# PhoneRinger_v1-2.net
KiCad netlist of a schematic drawn in EAGLE
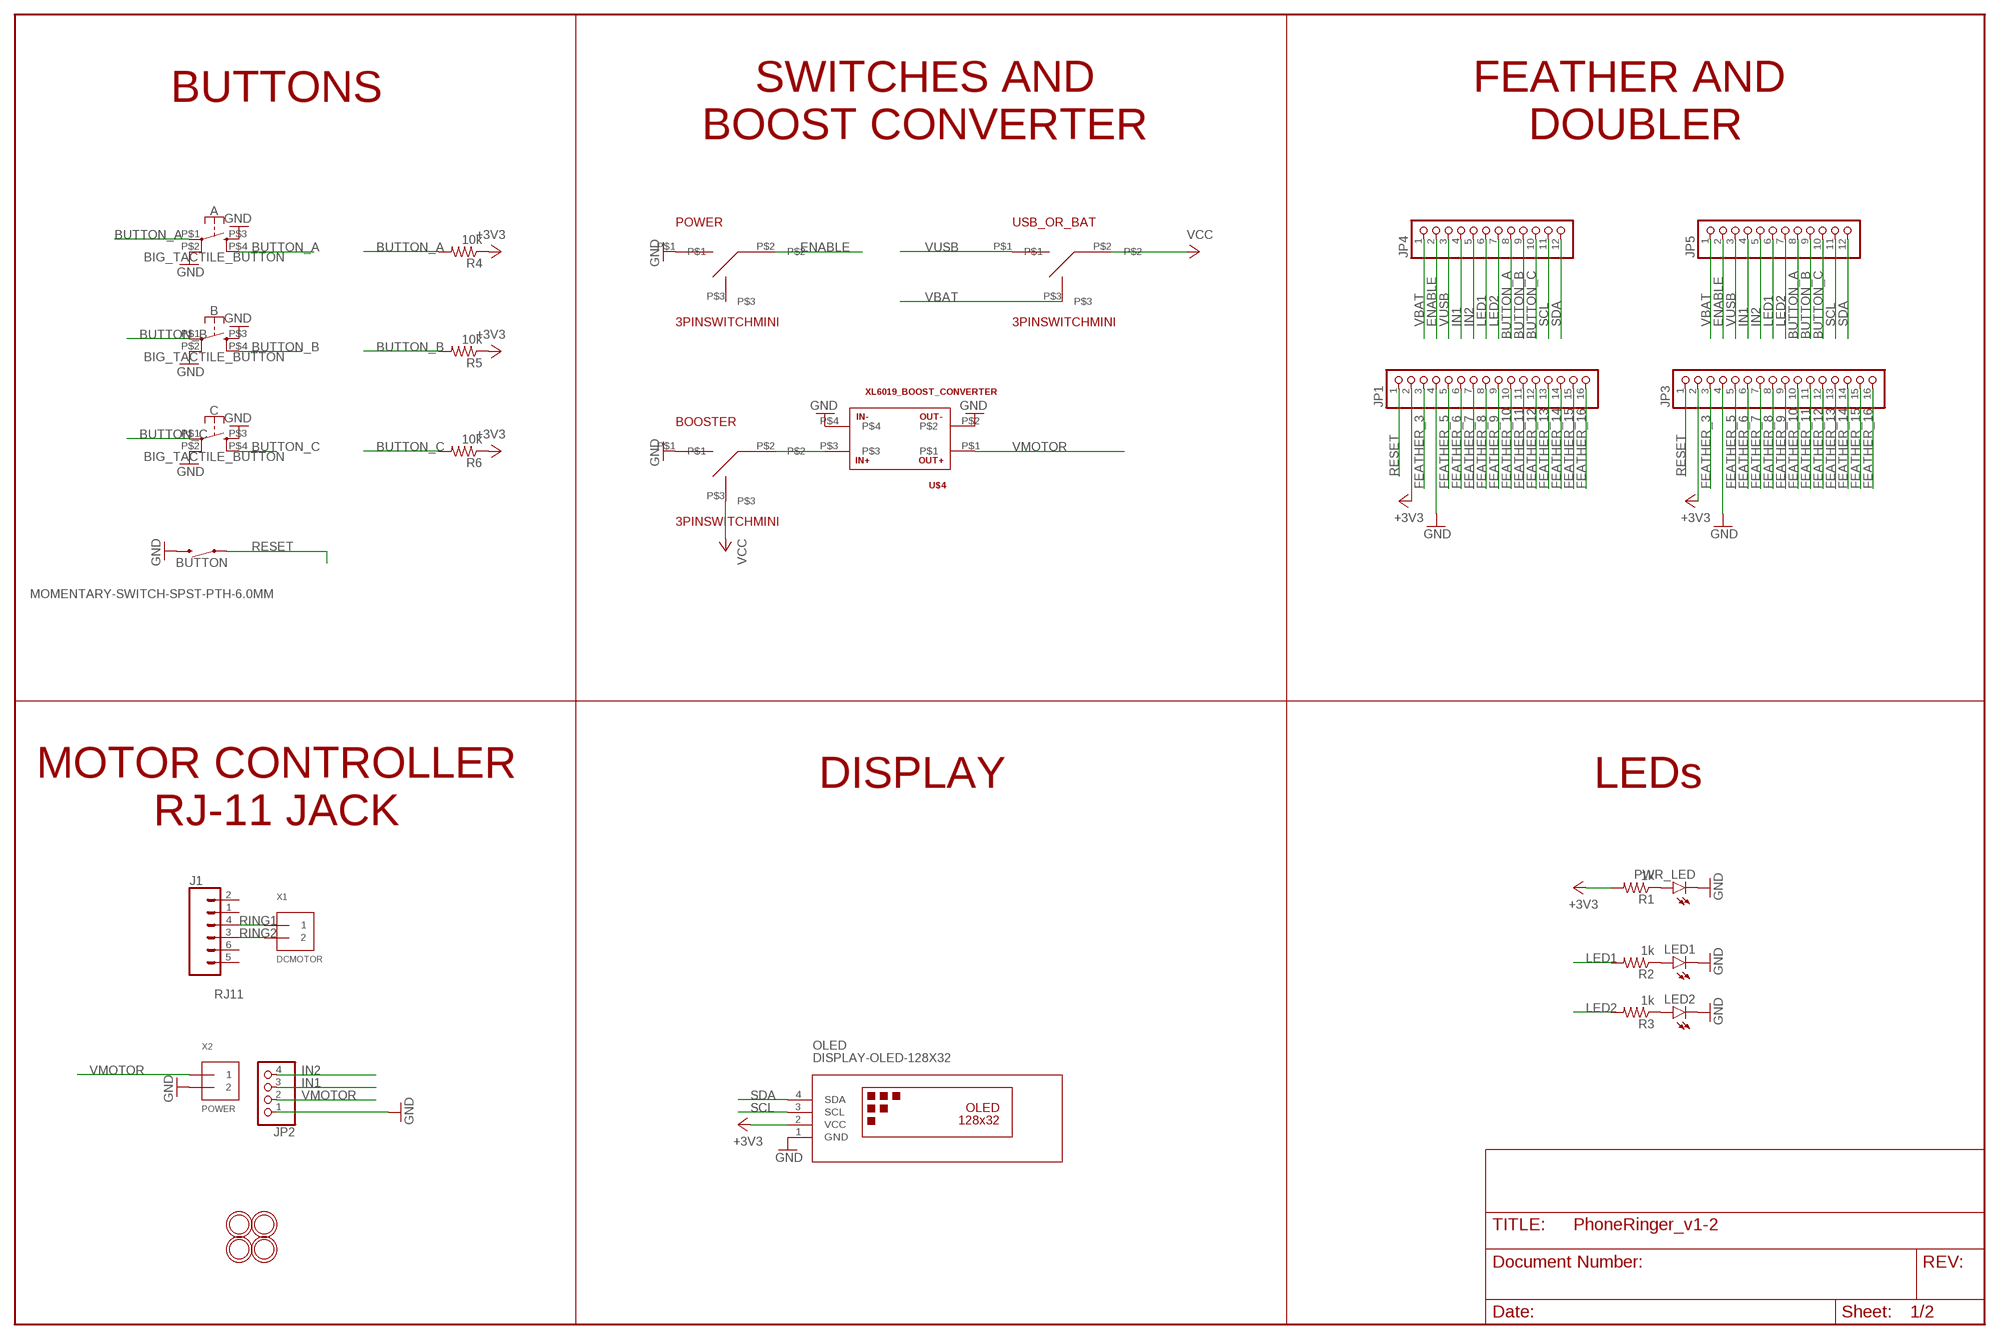
[diagram p0: schematic, sheet 1]

(export (version "E")
  (design (tool "Eeschema 10.0.6"))
  (components
    (comp (ref "A")
      (value "BIG_TACTILE_BUTTON")
      (footprint "eagle-import:BIG_TACTILE_BUTTON_FP")
      (libsource (lib "eagle-import") (part "BIG_TACTILE_BUTTON"))
    )
    (comp (ref "B")
      (value "BIG_TACTILE_BUTTON")
      (footprint "eagle-import:BIG_TACTILE_BUTTON_FP")
      (libsource (lib "eagle-import") (part "BIG_TACTILE_BUTTON"))
    )
    (comp (ref "BOOSTER")
      (value "3PINSWITCHMINI")
      (footprint "eagle-import:3PINMINI")
      (libsource (lib "eagle-import") (part "3PINSWITCHMINI"))
    )
    (comp (ref "BUTTON")
      (value "MOMENTARY-SWITCH-SPST-PTH-6.0MM")
      (footprint "eagle-import:TACTILE_SWITCH_PTH_6.0MM")
      (libsource (lib "eagle-import") (part "MOMENTARY-SWITCH-SPST-PTH-6.0MM"))
    )
    (comp (ref "C")
      (value "BIG_TACTILE_BUTTON")
      (footprint "eagle-import:BIG_TACTILE_BUTTON_FP")
      (libsource (lib "eagle-import") (part "BIG_TACTILE_BUTTON"))
    )
    (comp (ref "J1")
      (value "RJ11")
      (footprint "eagle-import:RJ11-6")
      (libsource (lib "eagle-import") (part "RJ11-6"))
    )
    (comp (ref "JP1")
      (value "HEADER-1X16_76MIL")
      (footprint "eagle-import:1X16_ROUND_76MIL")
      (libsource (lib "eagle-import") (part "HEADER-1X16_76MIL"))
    )
    (comp (ref "JP2")
      (value "HEADER-1X476MIL")
      (footprint "eagle-import:1X04_ROUND_76")
      (libsource (lib "eagle-import") (part "HEADER-1X476MIL"))
    )
    (comp (ref "JP3")
      (value "HEADER-1X16_76MIL")
      (footprint "eagle-import:1X16_ROUND_76MIL")
      (libsource (lib "eagle-import") (part "HEADER-1X16_76MIL"))
    )
    (comp (ref "JP4")
      (value "HEADER-1X1276MIL")
      (footprint "eagle-import:1X12_ROUND_76MIL")
      (libsource (lib "eagle-import") (part "HEADER-1X1276MIL"))
    )
    (comp (ref "JP5")
      (value "HEADER-1X1276MIL")
      (footprint "eagle-import:1X12_ROUND_76MIL")
      (libsource (lib "eagle-import") (part "HEADER-1X1276MIL"))
    )
    (comp (ref "LED1")
      (value "LED5MM")
      (footprint "eagle-import:LED5MM")
      (libsource (lib "eagle-import") (part "LED5MM"))
    )
    (comp (ref "LED2")
      (value "LED5MM")
      (footprint "eagle-import:LED5MM")
      (libsource (lib "eagle-import") (part "LED5MM"))
    )
    (comp (ref "OLED")
      (value "DISPLAY-OLED-128X32")
      (footprint "eagle-import:DISPLAY-OLED-128X32")
      (libsource (lib "eagle-import") (part "DISPLAY-OLED-128X32"))
    )
    (comp (ref "POWER")
      (value "3PINSWITCHMINI")
      (footprint "eagle-import:3PINMINI")
      (libsource (lib "eagle-import") (part "3PINSWITCHMINI"))
    )
    (comp (ref "PWR_LED")
      (value "LED5MM")
      (footprint "eagle-import:LED5MM")
      (libsource (lib "eagle-import") (part "LED5MM"))
    )
    (comp (ref "R1")
      (value "1k")
      (footprint "eagle-import:0207_10")
      (libsource (lib "eagle-import") (part "R-US_0207/10"))
    )
    (comp (ref "R2")
      (value "1k")
      (footprint "eagle-import:0207_10")
      (libsource (lib "eagle-import") (part "R-US_0207/10"))
    )
    (comp (ref "R3")
      (value "1k")
      (footprint "eagle-import:0207_10")
      (libsource (lib "eagle-import") (part "R-US_0207/10"))
    )
    (comp (ref "R4")
      (value "10k")
      (footprint "eagle-import:0207_10")
      (libsource (lib "eagle-import") (part "R-US_0207/10"))
    )
    (comp (ref "R5")
      (value "10k")
      (footprint "eagle-import:0207_10")
      (libsource (lib "eagle-import") (part "R-US_0207/10"))
    )
    (comp (ref "R6")
      (value "10k")
      (footprint "eagle-import:0207_10")
      (libsource (lib "eagle-import") (part "R-US_0207/10"))
    )
    (comp (ref "U$4")
      (value "XL6019_BOOST_CONVERTER")
      (footprint "eagle-import:XL6019_FP")
      (libsource (lib "eagle-import") (part "XL6019_BOOST_CONVERTER"))
    )
    (comp (ref "U$5")
      (value "MICROBUILDER_MOUNTINGHOLE2.5_THICK")
      (footprint "eagle-import:MICROBUILDER_MOUNTINGHOLE_2.5_PLATED_THICK")
      (libsource (lib "eagle-import") (part "MICROBUILDER_MOUNTINGHOLE2.5_THICK"))
    )
    (comp (ref "U$6")
      (value "MICROBUILDER_MOUNTINGHOLE2.5_THICK")
      (footprint "eagle-import:MICROBUILDER_MOUNTINGHOLE_2.5_PLATED_THICK")
      (libsource (lib "eagle-import") (part "MICROBUILDER_MOUNTINGHOLE2.5_THICK"))
    )
    (comp (ref "U$7")
      (value "MICROBUILDER_MOUNTINGHOLE2.5_THICK")
      (footprint "eagle-import:MICROBUILDER_MOUNTINGHOLE_2.5_PLATED_THICK")
      (libsource (lib "eagle-import") (part "MICROBUILDER_MOUNTINGHOLE2.5_THICK"))
    )
    (comp (ref "U$8")
      (value "MICROBUILDER_MOUNTINGHOLE2.5_THICK")
      (footprint "eagle-import:MICROBUILDER_MOUNTINGHOLE_2.5_PLATED_THICK")
      (libsource (lib "eagle-import") (part "MICROBUILDER_MOUNTINGHOLE2.5_THICK"))
    )
    (comp (ref "USB_OR_BAT")
      (value "3PINSWITCHMINI")
      (footprint "eagle-import:3PINMINI")
      (libsource (lib "eagle-import") (part "3PINSWITCHMINI"))
    )
    (comp (ref "X1")
      (value "DCMOTOR")
      (footprint "eagle-import:TERMBLOCK_1X2-3.5MM")
      (libsource (lib "eagle-import") (part "TERMBLOCK_1X2"))
    )
    (comp (ref "X2")
      (value "POWER")
      (footprint "eagle-import:TERMBLOCK_1X2-3.5MM")
      (libsource (lib "eagle-import") (part "TERMBLOCK_1X2"))
    )
  )
  (nets
    (net (code "1") (name "+3V3") (class "Default")
      (node (ref "JP1") (pin "2") (pinfunction "2_2") (pintype "passive"))
      (node (ref "JP3") (pin "2") (pinfunction "2_2") (pintype "passive"))
      (node (ref "OLED") (pin "2") (pinfunction "VCC_2") (pintype "power_in"))
      (node (ref "R1") (pin "2") (pinfunction "2_2") (pintype "passive"))
      (node (ref "R4") (pin "1") (pinfunction "1_1") (pintype "passive"))
      (node (ref "R5") (pin "1") (pinfunction "1_1") (pintype "passive"))
      (node (ref "R6") (pin "1") (pinfunction "1_1") (pintype "passive"))
    )
    (net (code "2") (name "BUTTON_A") (class "Default")
      (node (ref "A") (pin "P$1") (pinfunction "1_P$1") (pintype "passive"))
      (node (ref "A") (pin "P$4") (pinfunction "4_P$4") (pintype "passive"))
      (node (ref "JP4") (pin "8") (pinfunction "8_8") (pintype "passive"))
      (node (ref "JP5") (pin "8") (pinfunction "8_8") (pintype "passive"))
      (node (ref "R4") (pin "2") (pinfunction "2_2") (pintype "passive"))
    )
    (net (code "3") (name "BUTTON_B") (class "Default")
      (node (ref "B") (pin "P$1") (pinfunction "1_P$1") (pintype "passive"))
      (node (ref "B") (pin "P$4") (pinfunction "4_P$4") (pintype "passive"))
      (node (ref "JP4") (pin "9") (pinfunction "9_9") (pintype "passive"))
      (node (ref "JP5") (pin "9") (pinfunction "9_9") (pintype "passive"))
      (node (ref "R5") (pin "2") (pinfunction "2_2") (pintype "passive"))
    )
    (net (code "4") (name "BUTTON_C") (class "Default")
      (node (ref "C") (pin "P$1") (pinfunction "1_P$1") (pintype "passive"))
      (node (ref "C") (pin "P$4") (pinfunction "4_P$4") (pintype "passive"))
      (node (ref "JP4") (pin "10") (pinfunction "10_10") (pintype "passive"))
      (node (ref "JP5") (pin "10") (pinfunction "10_10") (pintype "passive"))
      (node (ref "R6") (pin "2") (pinfunction "2_2") (pintype "passive"))
    )
    (net (code "5") (name "ENABLE") (class "Default")
      (node (ref "JP4") (pin "2") (pinfunction "2_2") (pintype "passive"))
      (node (ref "JP5") (pin "2") (pinfunction "2_2") (pintype "passive"))
      (node (ref "POWER") (pin "P$2") (pinfunction "P$2_P$2") (pintype "bidirectional"))
    )
    (net (code "6") (name "FEATHER_3") (class "Default")
      (node (ref "JP1") (pin "3") (pinfunction "3_3") (pintype "passive"))
      (node (ref "JP3") (pin "3") (pinfunction "3_3") (pintype "passive"))
    )
    (net (code "7") (name "FEATHER_5") (class "Default")
      (node (ref "JP1") (pin "5") (pinfunction "5_5") (pintype "passive"))
      (node (ref "JP3") (pin "5") (pinfunction "5_5") (pintype "passive"))
    )
    (net (code "8") (name "FEATHER_6") (class "Default")
      (node (ref "JP1") (pin "6") (pinfunction "6_6") (pintype "passive"))
      (node (ref "JP3") (pin "6") (pinfunction "6_6") (pintype "passive"))
    )
    (net (code "9") (name "FEATHER_7") (class "Default")
      (node (ref "JP1") (pin "7") (pinfunction "7_7") (pintype "passive"))
      (node (ref "JP3") (pin "7") (pinfunction "7_7") (pintype "passive"))
    )
    (net (code "10") (name "FEATHER_8") (class "Default")
      (node (ref "JP1") (pin "8") (pinfunction "8_8") (pintype "passive"))
      (node (ref "JP3") (pin "8") (pinfunction "8_8") (pintype "passive"))
    )
    (net (code "11") (name "FEATHER_9") (class "Default")
      (node (ref "JP1") (pin "9") (pinfunction "9_9") (pintype "passive"))
      (node (ref "JP3") (pin "9") (pinfunction "9_9") (pintype "passive"))
    )
    (net (code "12") (name "FEATHER_10") (class "Default")
      (node (ref "JP1") (pin "10") (pinfunction "10_10") (pintype "passive"))
      (node (ref "JP3") (pin "10") (pinfunction "10_10") (pintype "passive"))
    )
    (net (code "13") (name "FEATHER_11") (class "Default")
      (node (ref "JP1") (pin "11") (pinfunction "11_11") (pintype "passive"))
      (node (ref "JP3") (pin "11") (pinfunction "11_11") (pintype "passive"))
    )
    (net (code "14") (name "FEATHER_12") (class "Default")
      (node (ref "JP1") (pin "12") (pinfunction "12_12") (pintype "passive"))
      (node (ref "JP3") (pin "12") (pinfunction "12_12") (pintype "passive"))
    )
    (net (code "15") (name "FEATHER_13") (class "Default")
      (node (ref "JP1") (pin "13") (pinfunction "13_13") (pintype "passive"))
      (node (ref "JP3") (pin "13") (pinfunction "13_13") (pintype "passive"))
    )
    (net (code "16") (name "FEATHER_14") (class "Default")
      (node (ref "JP1") (pin "14") (pinfunction "14_14") (pintype "passive"))
      (node (ref "JP3") (pin "14") (pinfunction "14_14") (pintype "passive"))
    )
    (net (code "17") (name "FEATHER_15") (class "Default")
      (node (ref "JP1") (pin "15") (pinfunction "15_15") (pintype "passive"))
      (node (ref "JP3") (pin "15") (pinfunction "15_15") (pintype "passive"))
    )
    (net (code "18") (name "FEATHER_16") (class "Default")
      (node (ref "JP1") (pin "16") (pinfunction "16_16") (pintype "passive"))
      (node (ref "JP3") (pin "16") (pinfunction "16_16") (pintype "passive"))
    )
    (net (code "19") (name "GND") (class "Default")
      (node (ref "A") (pin "P$2") (pinfunction "2_P$2") (pintype "passive"))
      (node (ref "A") (pin "P$3") (pinfunction "3_P$3") (pintype "passive"))
      (node (ref "B") (pin "P$2") (pinfunction "2_P$2") (pintype "passive"))
      (node (ref "B") (pin "P$3") (pinfunction "3_P$3") (pintype "passive"))
      (node (ref "BOOSTER") (pin "P$1") (pinfunction "P$1_P$1") (pintype "bidirectional"))
      (node (ref "BUTTON") (pin "3") (pinfunction "2_3") (pintype "passive"))
      (node (ref "C") (pin "P$2") (pinfunction "2_P$2") (pintype "passive"))
      (node (ref "C") (pin "P$3") (pinfunction "3_P$3") (pintype "passive"))
      (node (ref "JP1") (pin "4") (pinfunction "4_4") (pintype "passive"))
      (node (ref "JP2") (pin "1") (pinfunction "1_1") (pintype "passive"))
      (node (ref "JP3") (pin "4") (pinfunction "4_4") (pintype "passive"))
      (node (ref "LED1") (pin "K") (pinfunction "C_K") (pintype "passive"))
      (node (ref "LED2") (pin "K") (pinfunction "C_K") (pintype "passive"))
      (node (ref "OLED") (pin "1") (pinfunction "GND_1") (pintype "power_in"))
      (node (ref "POWER") (pin "P$1") (pinfunction "P$1_P$1") (pintype "bidirectional"))
      (node (ref "PWR_LED") (pin "K") (pinfunction "C_K") (pintype "passive"))
      (node (ref "U$4") (pin "P$2") (pinfunction "P$2_P$2") (pintype "bidirectional"))
      (node (ref "U$4") (pin "P$4") (pinfunction "P$4_P$4") (pintype "bidirectional"))
      (node (ref "X2") (pin "2") (pinfunction "2_2") (pintype "passive"))
    )
    (net (code "20") (name "IN1") (class "Default")
      (node (ref "JP2") (pin "3") (pinfunction "3_3") (pintype "passive"))
      (node (ref "JP4") (pin "4") (pinfunction "4_4") (pintype "passive"))
      (node (ref "JP5") (pin "4") (pinfunction "4_4") (pintype "passive"))
    )
    (net (code "21") (name "IN2") (class "Default")
      (node (ref "JP2") (pin "4") (pinfunction "4_4") (pintype "passive"))
      (node (ref "JP4") (pin "5") (pinfunction "5_5") (pintype "passive"))
      (node (ref "JP5") (pin "5") (pinfunction "5_5") (pintype "passive"))
    )
    (net (code "22") (name "LED1") (class "Default")
      (node (ref "JP4") (pin "6") (pinfunction "6_6") (pintype "passive"))
      (node (ref "JP5") (pin "6") (pinfunction "6_6") (pintype "passive"))
      (node (ref "R2") (pin "2") (pinfunction "2_2") (pintype "passive"))
    )
    (net (code "23") (name "LED2") (class "Default")
      (node (ref "JP4") (pin "7") (pinfunction "7_7") (pintype "passive"))
      (node (ref "JP5") (pin "7") (pinfunction "7_7") (pintype "passive"))
      (node (ref "R3") (pin "2") (pinfunction "2_2") (pintype "passive"))
    )
    (net (code "24") (name "Net-(BOOSTER-PadP$2)") (class "Default")
      (node (ref "BOOSTER") (pin "P$2") (pinfunction "P$2_P$2") (pintype "bidirectional"))
      (node (ref "U$4") (pin "P$3") (pinfunction "P$3_P$3") (pintype "bidirectional"))
    )
    (net (code "25") (name "Net-(LED1-PadA)") (class "Default")
      (node (ref "LED1") (pin "A") (pinfunction "A_A") (pintype "passive"))
      (node (ref "R2") (pin "1") (pinfunction "1_1") (pintype "passive"))
    )
    (net (code "26") (name "Net-(LED2-PadA)") (class "Default")
      (node (ref "LED2") (pin "A") (pinfunction "A_A") (pintype "passive"))
      (node (ref "R3") (pin "1") (pinfunction "1_1") (pintype "passive"))
    )
    (net (code "27") (name "Net-(PWR_LED-PadA)") (class "Default")
      (node (ref "PWR_LED") (pin "A") (pinfunction "A_A") (pintype "passive"))
      (node (ref "R1") (pin "1") (pinfunction "1_1") (pintype "passive"))
    )
    (net (code "28") (name "RESET") (class "Default")
      (node (ref "BUTTON") (pin "1") (pinfunction "1_1") (pintype "passive"))
      (node (ref "JP1") (pin "1") (pinfunction "1_1") (pintype "passive"))
      (node (ref "JP3") (pin "1") (pinfunction "1_1") (pintype "passive"))
    )
    (net (code "29") (name "RING1") (class "Default")
      (node (ref "J1") (pin "4") (pinfunction "4_4") (pintype "passive"))
      (node (ref "X1") (pin "1") (pinfunction "1_1") (pintype "passive"))
    )
    (net (code "30") (name "RING2") (class "Default")
      (node (ref "J1") (pin "3") (pinfunction "3_3") (pintype "passive"))
      (node (ref "X1") (pin "2") (pinfunction "2_2") (pintype "passive"))
    )
    (net (code "31") (name "SCL") (class "Default")
      (node (ref "JP4") (pin "11") (pinfunction "11_11") (pintype "passive"))
      (node (ref "JP5") (pin "11") (pinfunction "11_11") (pintype "passive"))
      (node (ref "OLED") (pin "3") (pinfunction "SCL_3") (pintype "bidirectional"))
    )
    (net (code "32") (name "SDA") (class "Default")
      (node (ref "JP4") (pin "12") (pinfunction "12_12") (pintype "passive"))
      (node (ref "JP5") (pin "12") (pinfunction "12_12") (pintype "passive"))
      (node (ref "OLED") (pin "4") (pinfunction "SDA_4") (pintype "bidirectional"))
    )
    (net (code "33") (name "VBAT") (class "Default")
      (node (ref "JP4") (pin "1") (pinfunction "1_1") (pintype "passive"))
      (node (ref "JP5") (pin "1") (pinfunction "1_1") (pintype "passive"))
      (node (ref "USB_OR_BAT") (pin "P$3") (pinfunction "P$3_P$3") (pintype "bidirectional"))
    )
    (net (code "34") (name "VCC") (class "Default")
      (node (ref "BOOSTER") (pin "P$3") (pinfunction "P$3_P$3") (pintype "bidirectional"))
      (node (ref "USB_OR_BAT") (pin "P$2") (pinfunction "P$2_P$2") (pintype "bidirectional"))
    )
    (net (code "35") (name "VMOTOR") (class "Default")
      (node (ref "JP2") (pin "2") (pinfunction "2_2") (pintype "passive"))
      (node (ref "U$4") (pin "P$1") (pinfunction "P$1_P$1") (pintype "bidirectional"))
      (node (ref "X2") (pin "1") (pinfunction "1_1") (pintype "passive"))
    )
    (net (code "36") (name "VUSB") (class "Default")
      (node (ref "JP4") (pin "3") (pinfunction "3_3") (pintype "passive"))
      (node (ref "JP5") (pin "3") (pinfunction "3_3") (pintype "passive"))
      (node (ref "USB_OR_BAT") (pin "P$1") (pinfunction "P$1_P$1") (pintype "bidirectional"))
    )
    (net (code "37") (name "unconnected-(J1-1-Pad5)") (class "Default")
      (node (ref "J1") (pin "5") (pinfunction "1_5") (pintype "passive"))
    )
    (net (code "38") (name "unconnected-(J1-2-Pad6)") (class "Default")
      (node (ref "J1") (pin "6") (pinfunction "2_6") (pintype "passive"))
    )
    (net (code "39") (name "unconnected-(J1-5-Pad1)") (class "Default")
      (node (ref "J1") (pin "1") (pinfunction "5_1") (pintype "passive"))
    )
    (net (code "40") (name "unconnected-(J1-6-Pad2)") (class "Default")
      (node (ref "J1") (pin "2") (pinfunction "6_2") (pintype "passive"))
    )
    (net (code "41") (name "unconnected-(POWER-PadP$3)") (class "Default")
      (node (ref "POWER") (pin "P$3") (pinfunction "P$3_P$3") (pintype "bidirectional"))
    )
  )
)
